# Son_of_Dark_Powersch.net
KiCad netlist of a schematic drawn in EAGLE
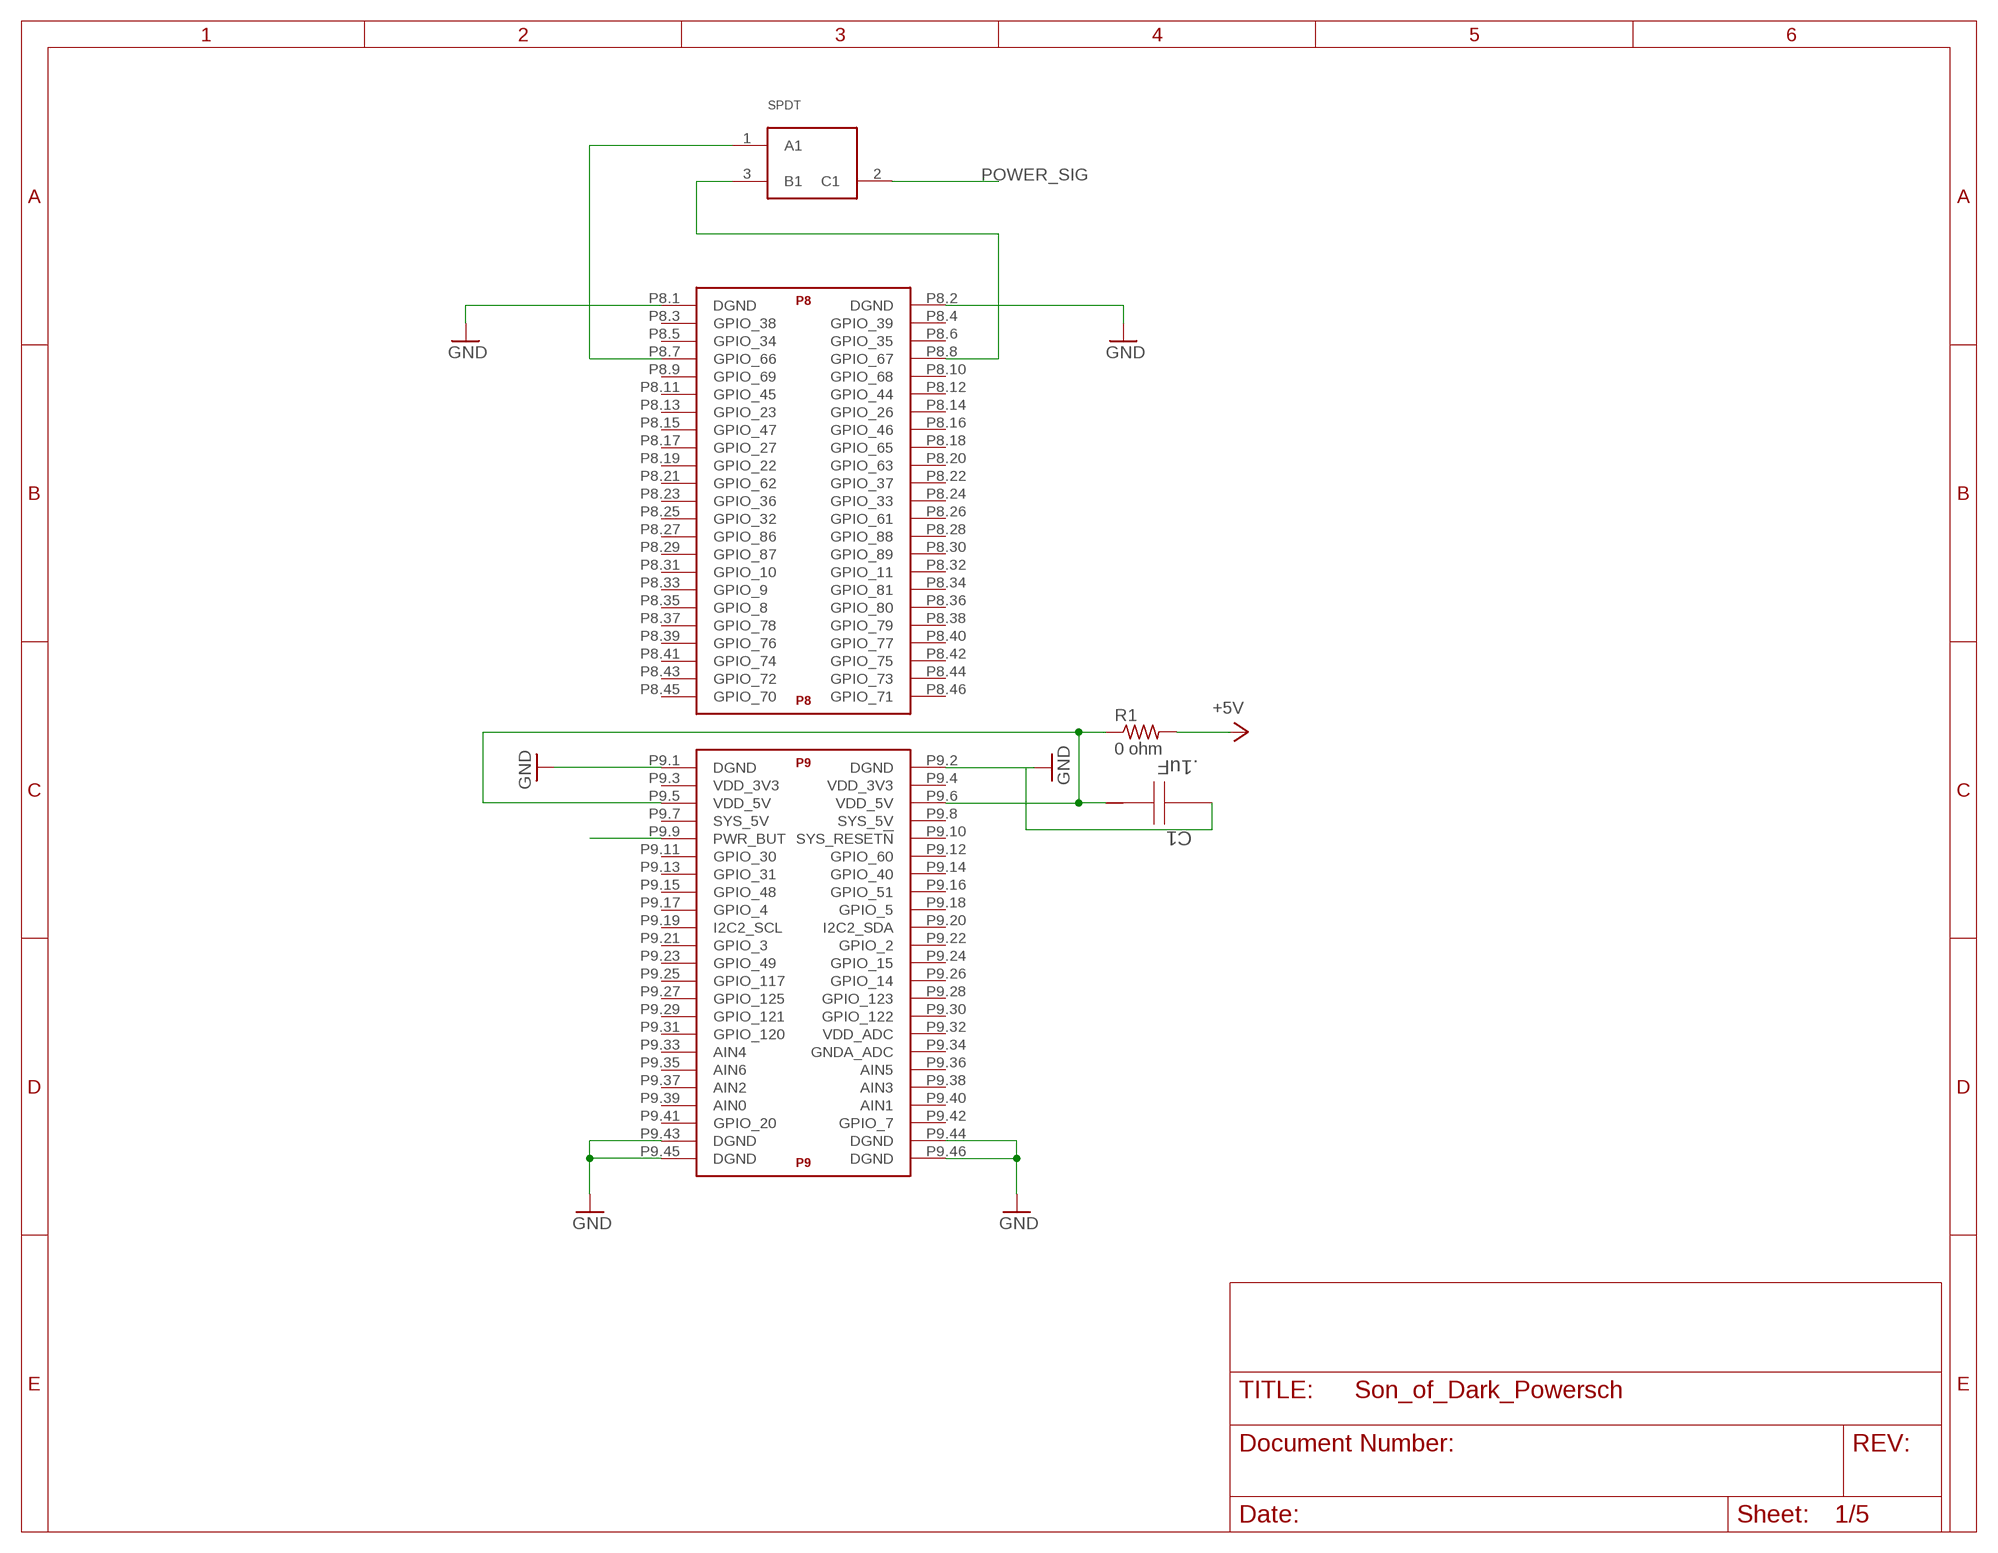
[diagram p0: schematic, sheet 1]
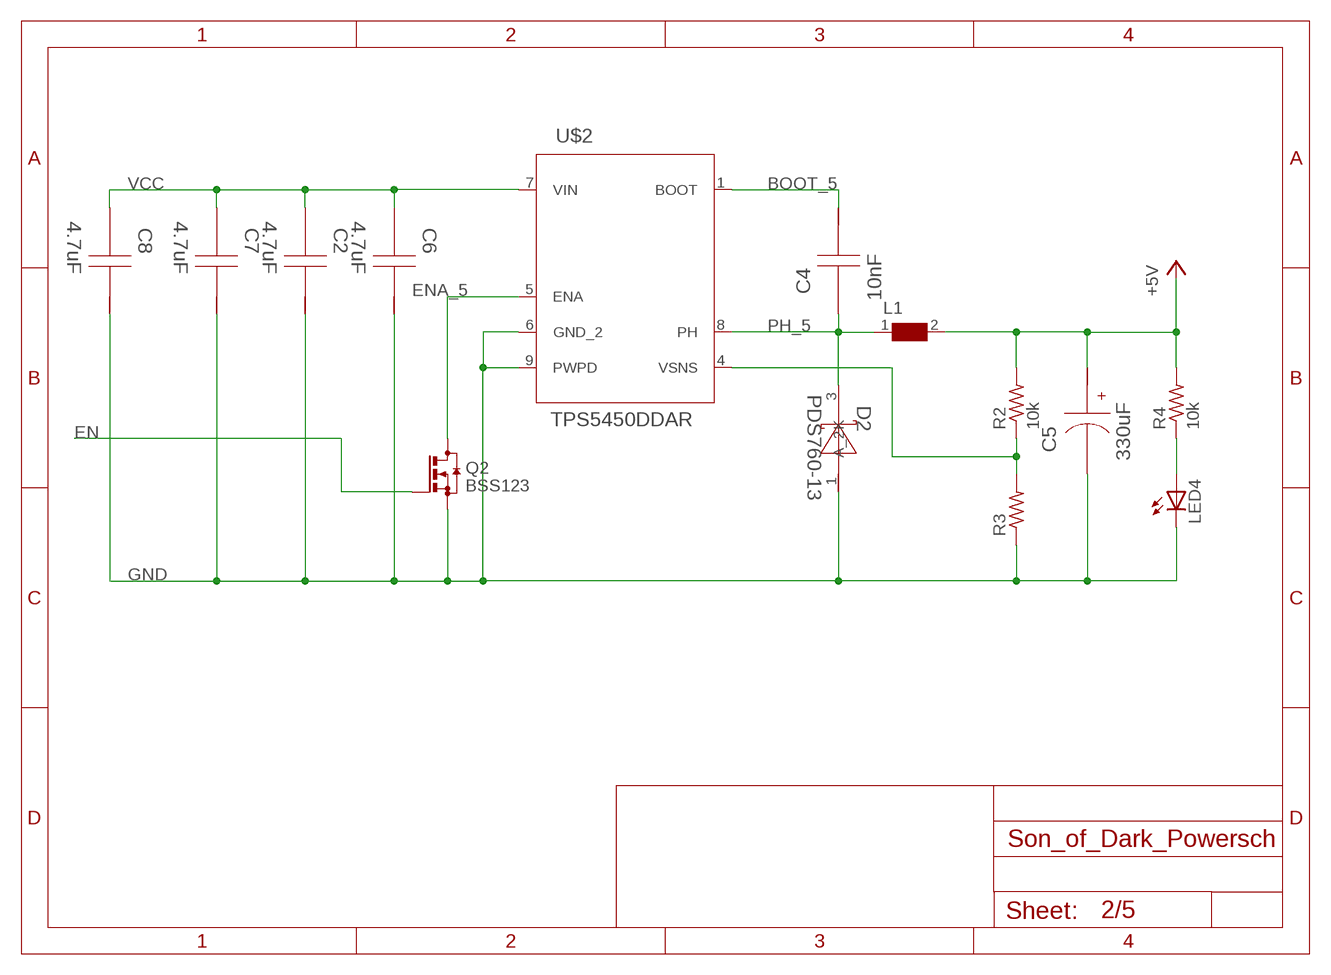
[diagram p1: schematic, sheet 2]
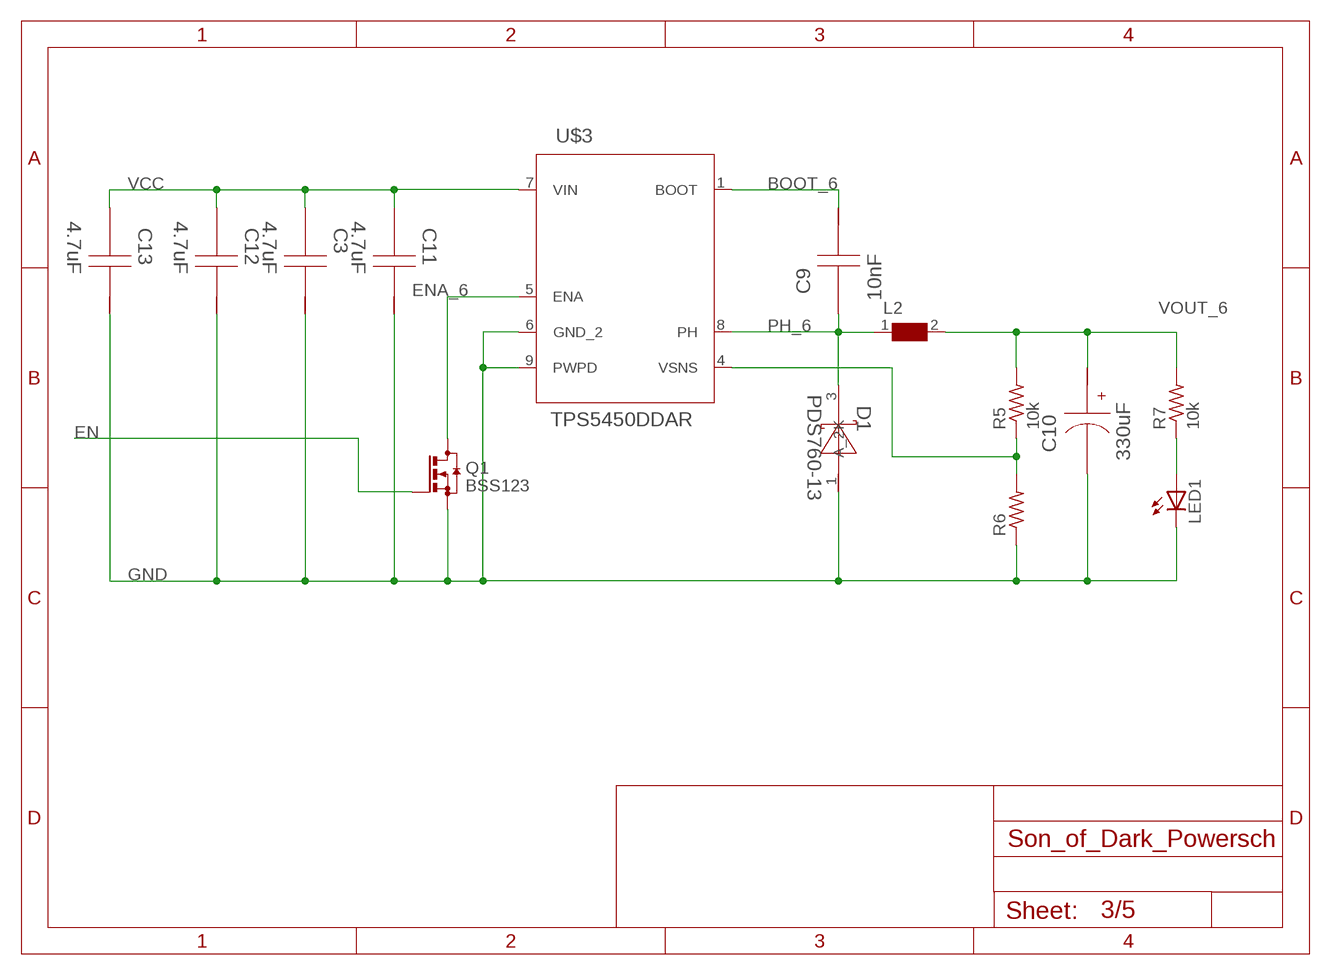
[diagram p2: schematic, sheet 3]
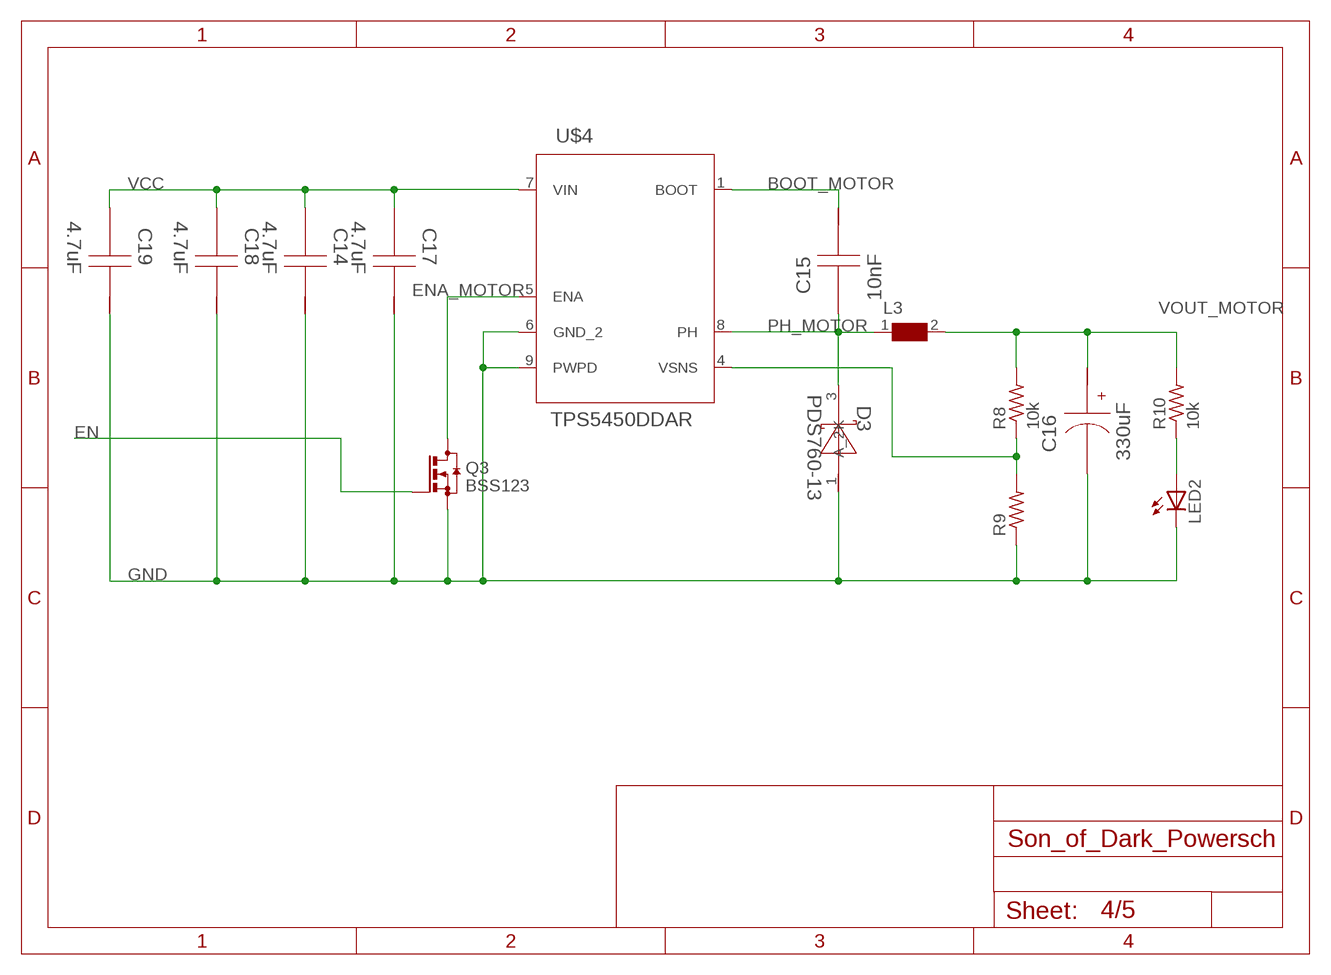
[diagram p3: schematic, sheet 4]
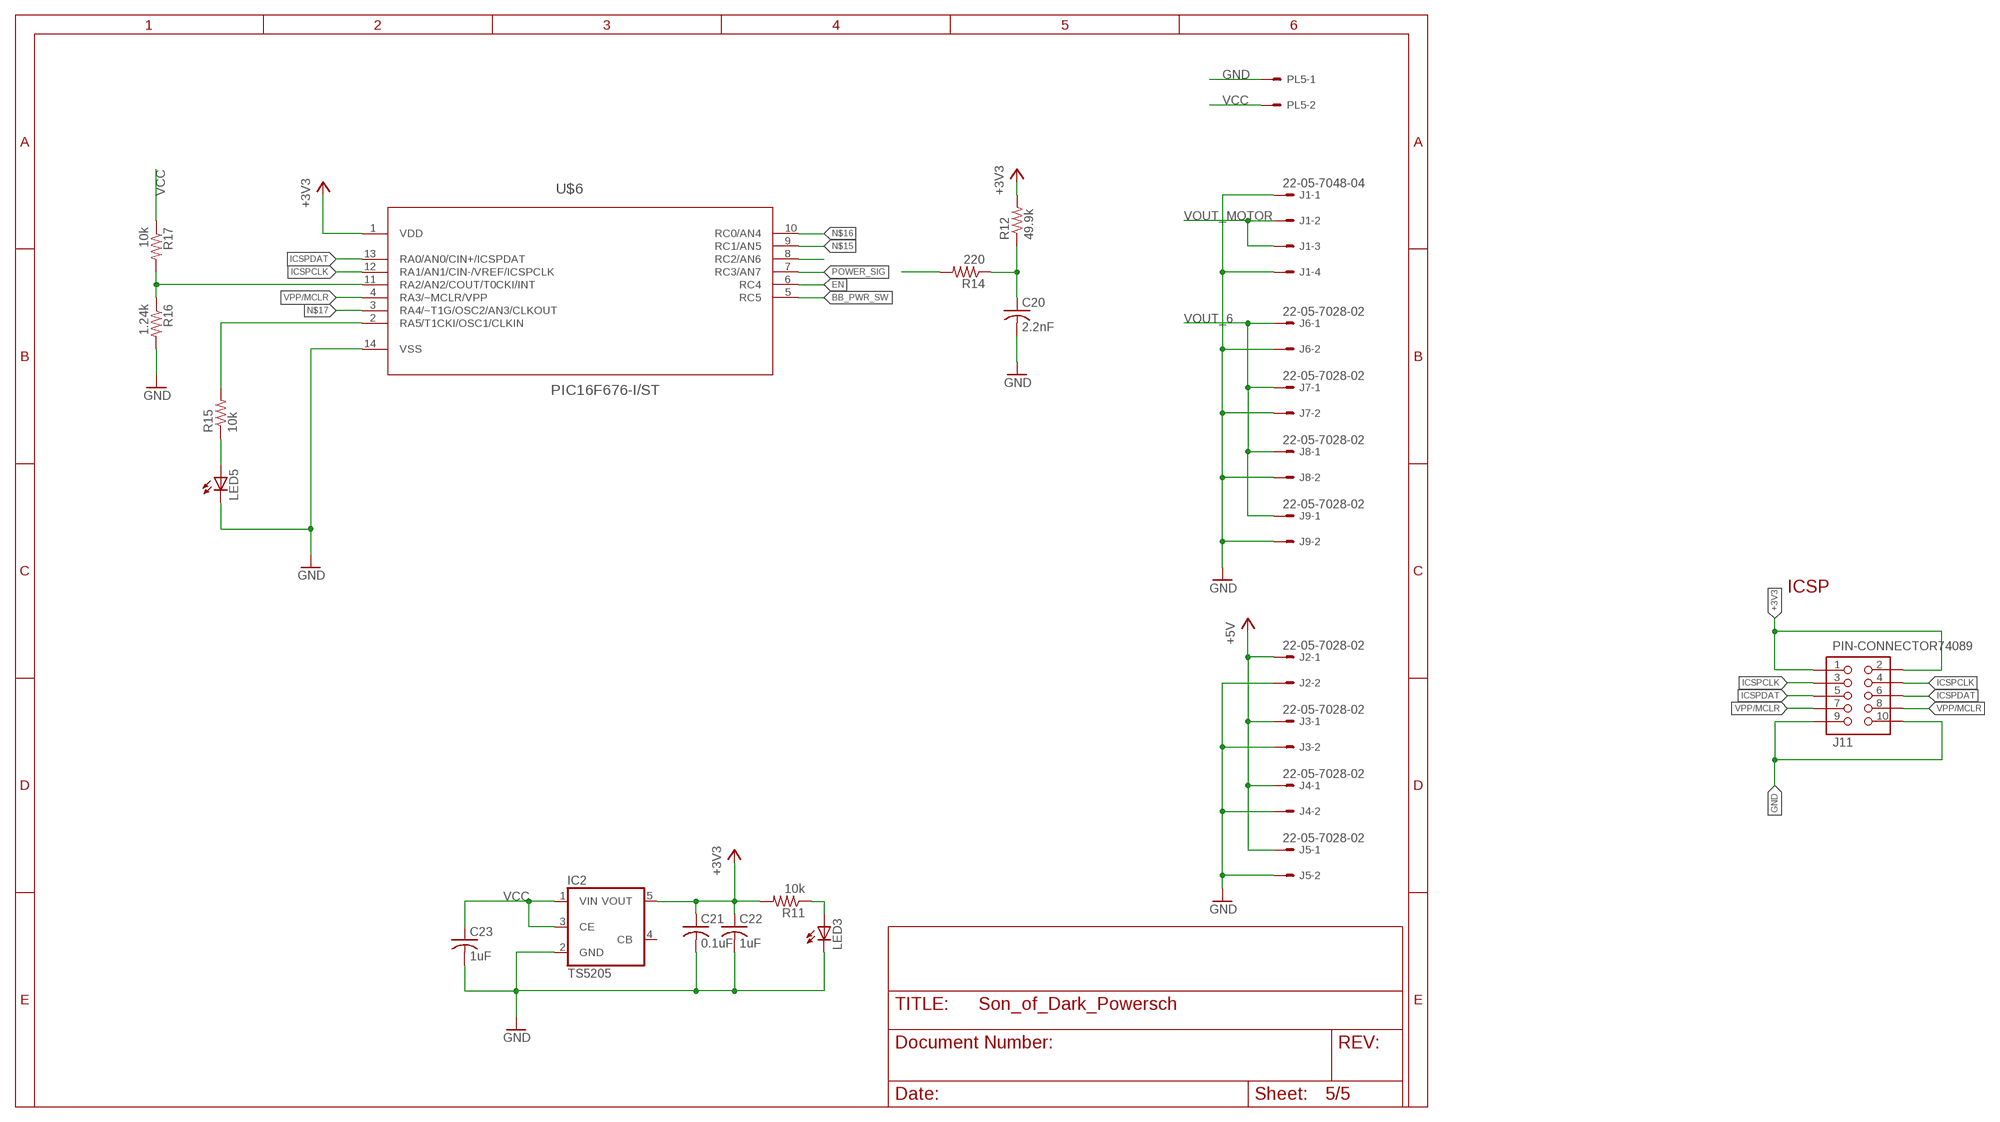
[diagram p4: schematic, sheet 5]

(export (version "E")
  (design (tool "Eeschema 10.0.6"))
  (components
    (comp (ref "C14")
      (value "4.7uF")
      (footprint "eagle-import:1206")
      (fields (field (name "MANUFACTURER_PART_NUMBER") "GRM31CR71H475KA12L"))
      (libsource (lib "eagle-import") (part "GRM31CR71H475KA12L"))
    )
    (comp (ref "C15")
      (value "10nF")
      (footprint "eagle-import:0805")
      (fields (field (name "MANUFACTURER_PART_NUMBER") "C0805C103K5RACTU"))
      (libsource (lib "eagle-import") (part "C0805C103K5RACTU"))
    )
    (comp (ref "C16")
      (value "330uF")
      (footprint "eagle-import:SM_RADIAL_10AMM")
      (fields (field (name "MANUFACTURER_PART_NUMBER") "10SVP330MX"))
      (libsource (lib "eagle-import") (part "10SVP330MX"))
    )
    (comp (ref "C17")
      (value "4.7uF")
      (footprint "eagle-import:1206")
      (fields (field (name "MANUFACTURER_PART_NUMBER") "GRM31CR71H475KA12L"))
      (libsource (lib "eagle-import") (part "GRM31CR71H475KA12L"))
    )
    (comp (ref "C18")
      (value "4.7uF")
      (footprint "eagle-import:1206")
      (fields (field (name "MANUFACTURER_PART_NUMBER") "GRM31CR71H475KA12L"))
      (libsource (lib "eagle-import") (part "GRM31CR71H475KA12L"))
    )
    (comp (ref "C19")
      (value "4.7uF")
      (footprint "eagle-import:1206")
      (fields (field (name "MANUFACTURER_PART_NUMBER") "GRM31CR71H475KA12L"))
      (libsource (lib "eagle-import") (part "GRM31CR71H475KA12L"))
    )
    (comp (ref "D3")
      (value "PDS760-13")
      (footprint "eagle-import:POWERDI5")
      (libsource (lib "eagle-import") (part "PDS760-13"))
    )
    (comp (ref "L3")
      (value "WE-HCC-7443331000_1090")
      (footprint "eagle-import:WE-HCC_1090")
      (fields (field (name "MPN") "7443331000"))
      (libsource (lib "eagle-import") (part "WE-HCC_1090-7443331000"))
    )
    (comp (ref "LED2")
      (value "LEDSML1206")
      (footprint "eagle-import:SML1206")
      (libsource (lib "eagle-import") (part "LEDSML1206"))
    )
    (comp (ref "Q3")
      (value "BSS123")
      (footprint "eagle-import:SOT23")
      (libsource (lib "eagle-import") (part "BSS123"))
    )
    (comp (ref "R8")
      (value "10k")
      (footprint "eagle-import:R1206")
      (libsource (lib "eagle-import") (part "R-US_R1206"))
    )
    (comp (ref "R9")
      (value "R-US_R1206")
      (footprint "eagle-import:R1206")
      (libsource (lib "eagle-import") (part "R-US_R1206"))
    )
    (comp (ref "R10")
      (value "10k")
      (footprint "eagle-import:R1206")
      (libsource (lib "eagle-import") (part "R-US_R1206"))
    )
    (comp (ref "U$4")
      (value "TPS5450DDAR")
      (footprint "eagle-import:R-PDSO-G8")
      (fields (field (name "MANUFACTURER_PART_NUMBER") "TPS5450DDA"))
      (libsource (lib "eagle-import") (part "TPS5450DDAR"))
    )
    (comp (ref "C20")
      (value "2.2nF")
      (footprint "eagle-import:C0603")
      (libsource (lib "eagle-import") (part "C-USC0603"))
    )
    (comp (ref "C21")
      (value "0.1uF")
      (footprint "eagle-import:C0603")
      (libsource (lib "eagle-import") (part "C-USC0603"))
    )
    (comp (ref "C22")
      (value "1uF")
      (footprint "eagle-import:C0603")
      (libsource (lib "eagle-import") (part "C-USC0603"))
    )
    (comp (ref "C23")
      (value "1uF")
      (footprint "eagle-import:C0603")
      (libsource (lib "eagle-import") (part "C-USC0603"))
    )
    (comp (ref "IC2")
      (value "TS5205")
      (footprint "eagle-import:SOT25")
      (libsource (lib "eagle-import") (part "TS5205"))
    )
    (comp (ref "J1")
      (value "22-05-7048-04")
      (footprint "eagle-import:7395-04")
      (libsource (lib "eagle-import") (part "22-?-0405-7048"))
    )
    (comp (ref "J2")
      (value "22-05-7028-02")
      (footprint "eagle-import:7395-02")
      (libsource (lib "eagle-import") (part "22-?-0205-7028"))
    )
    (comp (ref "J3")
      (value "22-05-7028-02")
      (footprint "eagle-import:7395-02")
      (libsource (lib "eagle-import") (part "22-?-0205-7028"))
    )
    (comp (ref "J4")
      (value "22-05-7028-02")
      (footprint "eagle-import:7395-02")
      (libsource (lib "eagle-import") (part "22-?-0205-7028"))
    )
    (comp (ref "J5")
      (value "22-05-7028-02")
      (footprint "eagle-import:7395-02")
      (libsource (lib "eagle-import") (part "22-?-0205-7028"))
    )
    (comp (ref "J6")
      (value "22-05-7028-02")
      (footprint "eagle-import:7395-02")
      (libsource (lib "eagle-import") (part "22-?-0205-7028"))
    )
    (comp (ref "J7")
      (value "22-05-7028-02")
      (footprint "eagle-import:7395-02")
      (libsource (lib "eagle-import") (part "22-?-0205-7028"))
    )
    (comp (ref "J8")
      (value "22-05-7028-02")
      (footprint "eagle-import:7395-02")
      (libsource (lib "eagle-import") (part "22-?-0205-7028"))
    )
    (comp (ref "J9")
      (value "22-05-7028-02")
      (footprint "eagle-import:7395-02")
      (libsource (lib "eagle-import") (part "22-?-0205-7028"))
    )
    (comp (ref "J11")
      (value "PIN-CONNECTOR74089")
      (footprint "eagle-import:10-PIN-SMD")
      (libsource (lib "eagle-import") (part "PIN-CONNECTOR74089"))
    )
    (comp (ref "LED3")
      (value "LEDSML1206")
      (footprint "eagle-import:SML1206")
      (libsource (lib "eagle-import") (part "LEDSML1206"))
    )
    (comp (ref "LED5")
      (value "LEDSML1206")
      (footprint "eagle-import:SML1206")
      (libsource (lib "eagle-import") (part "LEDSML1206"))
    )
    (comp (ref "PL5")
      (value "555X-2H")
      (footprint "eagle-import:5569-2")
      (libsource (lib "eagle-import") (part "555X-2H"))
    )
    (comp (ref "R11")
      (value "10k")
      (footprint "eagle-import:R1206")
      (libsource (lib "eagle-import") (part "R-US_R1206"))
    )
    (comp (ref "R12")
      (value "49.9k")
      (footprint "eagle-import:R0603")
      (libsource (lib "eagle-import") (part "R-US_R0603"))
    )
    (comp (ref "R14")
      (value "220")
      (footprint "eagle-import:R0603")
      (libsource (lib "eagle-import") (part "R-US_R0603"))
    )
    (comp (ref "R15")
      (value "10k")
      (footprint "eagle-import:R1206")
      (libsource (lib "eagle-import") (part "R-US_R1206"))
    )
    (comp (ref "R16")
      (value "1.24k")
      (footprint "eagle-import:R0603")
      (libsource (lib "eagle-import") (part "R-US_R0603"))
    )
    (comp (ref "R17")
      (value "10k")
      (footprint "eagle-import:R0603")
      (libsource (lib "eagle-import") (part "R-US_R0603"))
    )
    (comp (ref "U$6")
      (value "PIC16F676-I/ST")
      (footprint "eagle-import:SOP65P640X120-14N")
      (libsource (lib "eagle-import") (part "PIC16F676-I/ST"))
    )
    (comp (ref "C2")
      (value "4.7uF")
      (footprint "eagle-import:1206")
      (fields (field (name "MANUFACTURER_PART_NUMBER") "GRM31CR71H475KA12L"))
      (libsource (lib "eagle-import") (part "GRM31CR71H475KA12L"))
    )
    (comp (ref "C4")
      (value "10nF")
      (footprint "eagle-import:0805")
      (fields (field (name "MANUFACTURER_PART_NUMBER") "C0805C103K5RACTU"))
      (libsource (lib "eagle-import") (part "C0805C103K5RACTU"))
    )
    (comp (ref "C5")
      (value "330uF")
      (footprint "eagle-import:SM_RADIAL_10AMM")
      (fields (field (name "MANUFACTURER_PART_NUMBER") "10SVP330MX"))
      (libsource (lib "eagle-import") (part "10SVP330MX"))
    )
    (comp (ref "C6")
      (value "4.7uF")
      (footprint "eagle-import:1206")
      (fields (field (name "MANUFACTURER_PART_NUMBER") "GRM31CR71H475KA12L"))
      (libsource (lib "eagle-import") (part "GRM31CR71H475KA12L"))
    )
    (comp (ref "C7")
      (value "4.7uF")
      (footprint "eagle-import:1206")
      (fields (field (name "MANUFACTURER_PART_NUMBER") "GRM31CR71H475KA12L"))
      (libsource (lib "eagle-import") (part "GRM31CR71H475KA12L"))
    )
    (comp (ref "C8")
      (value "4.7uF")
      (footprint "eagle-import:1206")
      (fields (field (name "MANUFACTURER_PART_NUMBER") "GRM31CR71H475KA12L"))
      (libsource (lib "eagle-import") (part "GRM31CR71H475KA12L"))
    )
    (comp (ref "D2")
      (value "PDS760-13")
      (footprint "eagle-import:POWERDI5")
      (libsource (lib "eagle-import") (part "PDS760-13"))
    )
    (comp (ref "L1")
      (value "WE-HCC-7443331000_1090")
      (footprint "eagle-import:WE-HCC_1090")
      (fields (field (name "MPN") "7443331000"))
      (libsource (lib "eagle-import") (part "WE-HCC_1090-7443331000"))
    )
    (comp (ref "LED4")
      (value "LEDSML1206")
      (footprint "eagle-import:SML1206")
      (libsource (lib "eagle-import") (part "LEDSML1206"))
    )
    (comp (ref "Q2")
      (value "BSS123")
      (footprint "eagle-import:SOT23")
      (libsource (lib "eagle-import") (part "BSS123"))
    )
    (comp (ref "R2")
      (value "10k")
      (footprint "eagle-import:R1206")
      (libsource (lib "eagle-import") (part "R-US_R1206"))
    )
    (comp (ref "R3")
      (value "R-US_R1206")
      (footprint "eagle-import:R1206")
      (libsource (lib "eagle-import") (part "R-US_R1206"))
    )
    (comp (ref "R4")
      (value "10k")
      (footprint "eagle-import:R1206")
      (libsource (lib "eagle-import") (part "R-US_R1206"))
    )
    (comp (ref "U$2")
      (value "TPS5450DDAR")
      (footprint "eagle-import:R-PDSO-G8")
      (fields (field (name "MANUFACTURER_PART_NUMBER") "TPS5450DDA"))
      (libsource (lib "eagle-import") (part "TPS5450DDAR"))
    )
    (comp (ref "C3")
      (value "4.7uF")
      (footprint "eagle-import:1206")
      (fields (field (name "MANUFACTURER_PART_NUMBER") "GRM31CR71H475KA12L"))
      (libsource (lib "eagle-import") (part "GRM31CR71H475KA12L"))
    )
    (comp (ref "C9")
      (value "10nF")
      (footprint "eagle-import:0805")
      (fields (field (name "MANUFACTURER_PART_NUMBER") "C0805C103K5RACTU"))
      (libsource (lib "eagle-import") (part "C0805C103K5RACTU"))
    )
    (comp (ref "C10")
      (value "330uF")
      (footprint "eagle-import:SM_RADIAL_10AMM")
      (fields (field (name "MANUFACTURER_PART_NUMBER") "10SVP330MX"))
      (libsource (lib "eagle-import") (part "10SVP330MX"))
    )
    (comp (ref "C11")
      (value "4.7uF")
      (footprint "eagle-import:1206")
      (fields (field (name "MANUFACTURER_PART_NUMBER") "GRM31CR71H475KA12L"))
      (libsource (lib "eagle-import") (part "GRM31CR71H475KA12L"))
    )
    (comp (ref "C12")
      (value "4.7uF")
      (footprint "eagle-import:1206")
      (fields (field (name "MANUFACTURER_PART_NUMBER") "GRM31CR71H475KA12L"))
      (libsource (lib "eagle-import") (part "GRM31CR71H475KA12L"))
    )
    (comp (ref "C13")
      (value "4.7uF")
      (footprint "eagle-import:1206")
      (fields (field (name "MANUFACTURER_PART_NUMBER") "GRM31CR71H475KA12L"))
      (libsource (lib "eagle-import") (part "GRM31CR71H475KA12L"))
    )
    (comp (ref "D1")
      (value "PDS760-13")
      (footprint "eagle-import:POWERDI5")
      (libsource (lib "eagle-import") (part "PDS760-13"))
    )
    (comp (ref "L2")
      (value "WE-HCC-7443331000_1090")
      (footprint "eagle-import:WE-HCC_1090")
      (fields (field (name "MPN") "7443331000"))
      (libsource (lib "eagle-import") (part "WE-HCC_1090-7443331000"))
    )
    (comp (ref "LED1")
      (value "LEDSML1206")
      (footprint "eagle-import:SML1206")
      (libsource (lib "eagle-import") (part "LEDSML1206"))
    )
    (comp (ref "Q1")
      (value "BSS123")
      (footprint "eagle-import:SOT23")
      (libsource (lib "eagle-import") (part "BSS123"))
    )
    (comp (ref "R5")
      (value "10k")
      (footprint "eagle-import:R1206")
      (libsource (lib "eagle-import") (part "R-US_R1206"))
    )
    (comp (ref "R6")
      (value "R-US_R1206")
      (footprint "eagle-import:R1206")
      (libsource (lib "eagle-import") (part "R-US_R1206"))
    )
    (comp (ref "R7")
      (value "10k")
      (footprint "eagle-import:R1206")
      (libsource (lib "eagle-import") (part "R-US_R1206"))
    )
    (comp (ref "U$3")
      (value "TPS5450DDAR")
      (footprint "eagle-import:R-PDSO-G8")
      (fields (field (name "MANUFACTURER_PART_NUMBER") "TPS5450DDA"))
      (libsource (lib "eagle-import") (part "TPS5450DDAR"))
    )
    (comp (ref "C1")
      (value ".1uF")
      (footprint "eagle-import:1206")
      (fields (field (name "MANUFACTURER_PART_NUMBER") "C3216X5R1A106K"))
      (libsource (lib "eagle-import") (part "C3216X5R1A106K"))
    )
    (comp (ref "R1")
      (value "0 ohm")
      (footprint "eagle-import:R1206")
      (libsource (lib "eagle-import") (part "R-US_R1206"))
    )
    (comp (ref "SPDT")
      (value "SPDT_SWITCH")
      (footprint "eagle-import:SPDT")
      (libsource (lib "eagle-import") (part "SPDT_SWITCH"))
    )
    (comp (ref "U$1")
      (value "BEAGLE_BONE_BLACK_CAPE")
      (footprint "eagle-import:BEAGLE_BONE_BLACK_CAPE")
      (libsource (lib "eagle-import") (part "BEAGLE_BONE_BLACK_CAPE"))
    )
  )
  (nets
    (net (code "1") (name "+3V3") (class "Default")
      (node (ref "C21") (pin "1") (pinfunction "1_1") (pintype "passive"))
      (node (ref "C22") (pin "1") (pinfunction "1_1") (pintype "passive"))
      (node (ref "IC2") (pin "5") (pinfunction "VOUT_5") (pintype "passive"))
      (node (ref "J11") (pin "1") (pinfunction "P$1_1") (pintype "power_in"))
      (node (ref "J11") (pin "2") (pinfunction "P$2_2") (pintype "power_in"))
      (node (ref "R11") (pin "2") (pinfunction "2_2") (pintype "passive"))
      (node (ref "R12") (pin "2") (pinfunction "2_2") (pintype "passive"))
      (node (ref "U$6") (pin "1") (pinfunction "VDD_1") (pintype "power_in"))
    )
    (net (code "2") (name "+5V") (class "Default")
      (node (ref "C5") (pin "1") (pinfunction "+_1") (pintype "passive"))
      (node (ref "J2") (pin "1") (pinfunction "S_1") (pintype "passive"))
      (node (ref "J3") (pin "1") (pinfunction "S_1") (pintype "passive"))
      (node (ref "J4") (pin "1") (pinfunction "S_1") (pintype "passive"))
      (node (ref "J5") (pin "1") (pinfunction "S_1") (pintype "passive"))
      (node (ref "L1") (pin "2") (pinfunction "2_2") (pintype "passive"))
      (node (ref "R1") (pin "2") (pinfunction "2_2") (pintype "passive"))
      (node (ref "R2") (pin "2") (pinfunction "2_2") (pintype "passive"))
      (node (ref "R4") (pin "2") (pinfunction "2_2") (pintype "passive"))
    )
    (net (code "3") (name "BB_PWR_SW") (class "Default")
      (node (ref "U$1") (pin "P9.9") (pinfunction "PWR_BUT_P9.9") (pintype "bidirectional"))
      (node (ref "U$6") (pin "5") (pinfunction "RC5_5") (pintype "bidirectional"))
    )
    (net (code "4") (name "BOOT_5") (class "Default")
      (node (ref "C4") (pin "1") (pinfunction "1_1") (pintype "passive"))
      (node (ref "U$2") (pin "1") (pinfunction "BOOT_1") (pintype "passive"))
    )
    (net (code "5") (name "BOOT_6") (class "Default")
      (node (ref "C9") (pin "1") (pinfunction "1_1") (pintype "passive"))
      (node (ref "U$3") (pin "1") (pinfunction "BOOT_1") (pintype "passive"))
    )
    (net (code "6") (name "BOOT_MOTOR") (class "Default")
      (node (ref "C15") (pin "1") (pinfunction "1_1") (pintype "passive"))
      (node (ref "U$4") (pin "1") (pinfunction "BOOT_1") (pintype "passive"))
    )
    (net (code "7") (name "EN") (class "Default")
      (node (ref "Q1") (pin "1") (pinfunction "G_1") (pintype "passive"))
      (node (ref "Q2") (pin "1") (pinfunction "G_1") (pintype "passive"))
      (node (ref "Q3") (pin "1") (pinfunction "G_1") (pintype "passive"))
      (node (ref "U$6") (pin "6") (pinfunction "RC4_6") (pintype "bidirectional"))
    )
    (net (code "8") (name "ENA_5") (class "Default")
      (node (ref "Q2") (pin "3") (pinfunction "D_3") (pintype "passive"))
      (node (ref "U$2") (pin "5") (pinfunction "ENA_5") (pintype "passive"))
    )
    (net (code "9") (name "ENA_6") (class "Default")
      (node (ref "Q1") (pin "3") (pinfunction "D_3") (pintype "passive"))
      (node (ref "U$3") (pin "5") (pinfunction "ENA_5") (pintype "passive"))
    )
    (net (code "10") (name "ENA_MOTOR") (class "Default")
      (node (ref "Q3") (pin "3") (pinfunction "D_3") (pintype "passive"))
      (node (ref "U$4") (pin "5") (pinfunction "ENA_5") (pintype "passive"))
    )
    (net (code "11") (name "GND") (class "Default")
      (node (ref "C1") (pin "2") (pinfunction "2_2") (pintype "passive"))
      (node (ref "C10") (pin "2") (pinfunction "-_2") (pintype "passive"))
      (node (ref "C11") (pin "1") (pinfunction "1_1") (pintype "passive"))
      (node (ref "C12") (pin "1") (pinfunction "1_1") (pintype "passive"))
      (node (ref "C13") (pin "1") (pinfunction "1_1") (pintype "passive"))
      (node (ref "C14") (pin "1") (pinfunction "1_1") (pintype "passive"))
      (node (ref "C16") (pin "2") (pinfunction "-_2") (pintype "passive"))
      (node (ref "C17") (pin "1") (pinfunction "1_1") (pintype "passive"))
      (node (ref "C18") (pin "1") (pinfunction "1_1") (pintype "passive"))
      (node (ref "C19") (pin "1") (pinfunction "1_1") (pintype "passive"))
      (node (ref "C2") (pin "1") (pinfunction "1_1") (pintype "passive"))
      (node (ref "C20") (pin "2") (pinfunction "2_2") (pintype "passive"))
      (node (ref "C21") (pin "2") (pinfunction "2_2") (pintype "passive"))
      (node (ref "C22") (pin "2") (pinfunction "2_2") (pintype "passive"))
      (node (ref "C23") (pin "2") (pinfunction "2_2") (pintype "passive"))
      (node (ref "C3") (pin "1") (pinfunction "1_1") (pintype "passive"))
      (node (ref "C5") (pin "2") (pinfunction "-_2") (pintype "passive"))
      (node (ref "C6") (pin "1") (pinfunction "1_1") (pintype "passive"))
      (node (ref "C7") (pin "1") (pinfunction "1_1") (pintype "passive"))
      (node (ref "C8") (pin "1") (pinfunction "1_1") (pintype "passive"))
      (node (ref "D1") (pin "1") (pinfunction "A_2_1") (pintype "passive"))
      (node (ref "D2") (pin "1") (pinfunction "A_2_1") (pintype "passive"))
      (node (ref "D3") (pin "1") (pinfunction "A_2_1") (pintype "passive"))
      (node (ref "IC2") (pin "2") (pinfunction "GND_2") (pintype "passive"))
      (node (ref "J1") (pin "1") (pinfunction "S_1") (pintype "passive"))
      (node (ref "J1") (pin "4") (pinfunction "S_4") (pintype "passive"))
      (node (ref "J11") (pin "10") (pinfunction "P$10_10") (pintype "power_in"))
      (node (ref "J11") (pin "9") (pinfunction "P$9_9") (pintype "power_in"))
      (node (ref "J2") (pin "2") (pinfunction "S_2") (pintype "passive"))
      (node (ref "J3") (pin "2") (pinfunction "S_2") (pintype "passive"))
      (node (ref "J4") (pin "2") (pinfunction "S_2") (pintype "passive"))
      (node (ref "J5") (pin "2") (pinfunction "S_2") (pintype "passive"))
      (node (ref "J6") (pin "2") (pinfunction "S_2") (pintype "passive"))
      (node (ref "J7") (pin "2") (pinfunction "S_2") (pintype "passive"))
      (node (ref "J8") (pin "2") (pinfunction "S_2") (pintype "passive"))
      (node (ref "J9") (pin "2") (pinfunction "S_2") (pintype "passive"))
      (node (ref "LED1") (pin "C") (pinfunction "C_C") (pintype "passive"))
      (node (ref "LED2") (pin "C") (pinfunction "C_C") (pintype "passive"))
      (node (ref "LED3") (pin "C") (pinfunction "C_C") (pintype "passive"))
      (node (ref "LED4") (pin "C") (pinfunction "C_C") (pintype "passive"))
      (node (ref "LED5") (pin "C") (pinfunction "C_C") (pintype "passive"))
      (node (ref "PL5") (pin "1") (pinfunction "S_1") (pintype "passive"))
      (node (ref "Q1") (pin "2") (pinfunction "S_2") (pintype "passive"))
      (node (ref "Q2") (pin "2") (pinfunction "S_2") (pintype "passive"))
      (node (ref "Q3") (pin "2") (pinfunction "S_2") (pintype "passive"))
      (node (ref "R16") (pin "2") (pinfunction "2_2") (pintype "passive"))
      (node (ref "R3") (pin "1") (pinfunction "1_1") (pintype "passive"))
      (node (ref "R6") (pin "1") (pinfunction "1_1") (pintype "passive"))
      (node (ref "R9") (pin "1") (pinfunction "1_1") (pintype "passive"))
      (node (ref "U$1") (pin "P8.1") (pinfunction "DGND_P8.1") (pintype "bidirectional"))
      (node (ref "U$1") (pin "P8.2") (pinfunction "DGND_P8.2") (pintype "bidirectional"))
      (node (ref "U$1") (pin "P9.1") (pinfunction "DGND_P9.1") (pintype "bidirectional"))
      (node (ref "U$1") (pin "P9.2") (pinfunction "DGND_P9.2") (pintype "bidirectional"))
      (node (ref "U$1") (pin "P9.43") (pinfunction "DGND_P9.43") (pintype "bidirectional"))
      (node (ref "U$1") (pin "P9.44") (pinfunction "DGND_P9.44") (pintype "bidirectional"))
      (node (ref "U$1") (pin "P9.45") (pinfunction "DGND_P9.45") (pintype "bidirectional"))
      (node (ref "U$1") (pin "P9.46") (pinfunction "DGND_P9.46") (pintype "bidirectional"))
      (node (ref "U$2") (pin "6") (pinfunction "GND_2_6") (pintype "passive"))
      (node (ref "U$2") (pin "9") (pinfunction "PWPD_9") (pintype "passive"))
      (node (ref "U$3") (pin "6") (pinfunction "GND_2_6") (pintype "passive"))
      (node (ref "U$3") (pin "9") (pinfunction "PWPD_9") (pintype "passive"))
      (node (ref "U$4") (pin "6") (pinfunction "GND_2_6") (pintype "passive"))
      (node (ref "U$4") (pin "9") (pinfunction "PWPD_9") (pintype "passive"))
      (node (ref "U$6") (pin "14") (pinfunction "VSS_14") (pintype "power_in"))
    )
    (net (code "12") (name "ICSPCLK") (class "Default")
      (node (ref "J11") (pin "3") (pinfunction "P$3_3") (pintype "power_in"))
      (node (ref "J11") (pin "4") (pinfunction "P$4_4") (pintype "power_in"))
      (node (ref "U$6") (pin "12") (pinfunction "RA1/AN1/CIN-/VREF/ICSPCLK_12") (pintype "bidirectional"))
    )
    (net (code "13") (name "ICSPDAT") (class "Default")
      (node (ref "J11") (pin "5") (pinfunction "P$5_5") (pintype "power_in"))
      (node (ref "J11") (pin "6") (pinfunction "P$6_6") (pintype "power_in"))
      (node (ref "U$6") (pin "13") (pinfunction "RA0/AN0/CIN+/ICSPDAT_13") (pintype "bidirectional"))
    )
    (net (code "14") (name "N$15") (class "Default")
      (node (ref "U$6") (pin "9") (pinfunction "RC1/AN5_9") (pintype "bidirectional"))
    )
    (net (code "15") (name "N$16") (class "Default")
      (node (ref "U$6") (pin "10") (pinfunction "RC0/AN4_10") (pintype "bidirectional"))
    )
    (net (code "16") (name "N$17") (class "Default")
      (node (ref "U$6") (pin "3") (pinfunction "RA4/~{T1G/OSC2/AN3/CLKOUT}_3") (pintype "bidirectional"))
    )
    (net (code "17") (name "Net-(C1-Pad1)") (class "Default")
      (node (ref "C1") (pin "1") (pinfunction "1_1") (pintype "passive"))
      (node (ref "R1") (pin "1") (pinfunction "1_1") (pintype "passive"))
      (node (ref "U$1") (pin "P9.5") (pinfunction "VDD_5V_P9.5") (pintype "bidirectional"))
      (node (ref "U$1") (pin "P9.6") (pinfunction "VDD_5V_P9.6") (pintype "bidirectional"))
    )
    (net (code "18") (name "Net-(C20-Pad1)") (class "Default")
      (node (ref "C20") (pin "1") (pinfunction "1_1") (pintype "passive"))
      (node (ref "R12") (pin "1") (pinfunction "1_1") (pintype "passive"))
      (node (ref "R14") (pin "1") (pinfunction "1_1") (pintype "passive"))
    )
    (net (code "19") (name "Net-(LED1-PadA)") (class "Default")
      (node (ref "LED1") (pin "A") (pinfunction "A_A") (pintype "passive"))
      (node (ref "R7") (pin "1") (pinfunction "1_1") (pintype "passive"))
    )
    (net (code "20") (name "Net-(LED2-PadA)") (class "Default")
      (node (ref "LED2") (pin "A") (pinfunction "A_A") (pintype "passive"))
      (node (ref "R10") (pin "1") (pinfunction "1_1") (pintype "passive"))
    )
    (net (code "21") (name "Net-(LED3-PadA)") (class "Default")
      (node (ref "LED3") (pin "A") (pinfunction "A_A") (pintype "passive"))
      (node (ref "R11") (pin "1") (pinfunction "1_1") (pintype "passive"))
    )
    (net (code "22") (name "Net-(LED4-PadA)") (class "Default")
      (node (ref "LED4") (pin "A") (pinfunction "A_A") (pintype "passive"))
      (node (ref "R4") (pin "1") (pinfunction "1_1") (pintype "passive"))
    )
    (net (code "23") (name "Net-(LED5-PadA)") (class "Default")
      (node (ref "LED5") (pin "A") (pinfunction "A_A") (pintype "passive"))
      (node (ref "R15") (pin "1") (pinfunction "1_1") (pintype "passive"))
    )
    (net (code "24") (name "Net-(SPDT-A1)") (class "Default")
      (node (ref "SPDT") (pin "1") (pinfunction "A1_1") (pintype "bidirectional"))
      (node (ref "U$1") (pin "P8.7") (pinfunction "GPIO_66_P8.7") (pintype "bidirectional"))
    )
    (net (code "25") (name "Net-(SPDT-B1)") (class "Default")
      (node (ref "SPDT") (pin "3") (pinfunction "B1_3") (pintype "bidirectional"))
      (node (ref "U$1") (pin "P8.8") (pinfunction "GPIO_67_P8.8") (pintype "bidirectional"))
    )
    (net (code "26") (name "Net-(U$2-VSNS)") (class "Default")
      (node (ref "R2") (pin "1") (pinfunction "1_1") (pintype "passive"))
      (node (ref "R3") (pin "2") (pinfunction "2_2") (pintype "passive"))
      (node (ref "U$2") (pin "4") (pinfunction "VSNS_4") (pintype "passive"))
    )
    (net (code "27") (name "Net-(U$3-VSNS)") (class "Default")
      (node (ref "R5") (pin "1") (pinfunction "1_1") (pintype "passive"))
      (node (ref "R6") (pin "2") (pinfunction "2_2") (pintype "passive"))
      (node (ref "U$3") (pin "4") (pinfunction "VSNS_4") (pintype "passive"))
    )
    (net (code "28") (name "Net-(U$4-VSNS)") (class "Default")
      (node (ref "R8") (pin "1") (pinfunction "1_1") (pintype "passive"))
      (node (ref "R9") (pin "2") (pinfunction "2_2") (pintype "passive"))
      (node (ref "U$4") (pin "4") (pinfunction "VSNS_4") (pintype "passive"))
    )
    (net (code "29") (name "Net-(U$6-RA2{slash}AN2{slash}COUT{slash}T0CKI{slash}INT)") (class "Default")
      (node (ref "R16") (pin "1") (pinfunction "1_1") (pintype "passive"))
      (node (ref "R17") (pin "2") (pinfunction "2_2") (pintype "passive"))
      (node (ref "U$6") (pin "11") (pinfunction "RA2/AN2/COUT/T0CKI/INT_11") (pintype "bidirectional"))
    )
    (net (code "30") (name "Net-(U$6-RA5{slash}T1CKI{slash}OSC1{slash}CLKIN)") (class "Default")
      (node (ref "R15") (pin "2") (pinfunction "2_2") (pintype "passive"))
      (node (ref "U$6") (pin "2") (pinfunction "RA5/T1CKI/OSC1/CLKIN_2") (pintype "bidirectional"))
    )
    (net (code "31") (name "PH_5") (class "Default")
      (node (ref "C4") (pin "2") (pinfunction "2_2") (pintype "passive"))
      (node (ref "D2") (pin "3") (pinfunction "K_3") (pintype "passive"))
      (node (ref "L1") (pin "1") (pinfunction "1_1") (pintype "passive"))
      (node (ref "U$2") (pin "8") (pinfunction "PH_8") (pintype "passive"))
    )
    (net (code "32") (name "PH_6") (class "Default")
      (node (ref "C9") (pin "2") (pinfunction "2_2") (pintype "passive"))
      (node (ref "D1") (pin "3") (pinfunction "K_3") (pintype "passive"))
      (node (ref "L2") (pin "1") (pinfunction "1_1") (pintype "passive"))
      (node (ref "U$3") (pin "8") (pinfunction "PH_8") (pintype "passive"))
    )
    (net (code "33") (name "PH_MOTOR") (class "Default")
      (node (ref "C15") (pin "2") (pinfunction "2_2") (pintype "passive"))
      (node (ref "D3") (pin "3") (pinfunction "K_3") (pintype "passive"))
      (node (ref "L3") (pin "1") (pinfunction "1_1") (pintype "passive"))
      (node (ref "U$4") (pin "8") (pinfunction "PH_8") (pintype "passive"))
    )
    (net (code "34") (name "POWER_SIG") (class "Default")
      (node (ref "SPDT") (pin "2") (pinfunction "C1_2") (pintype "bidirectional"))
      (node (ref "U$6") (pin "7") (pinfunction "RC3/AN7_7") (pintype "bidirectional"))
    )
    (net (code "35") (name "VCC") (class "Default")
      (node (ref "C11") (pin "2") (pinfunction "2_2") (pintype "passive"))
      (node (ref "C12") (pin "2") (pinfunction "2_2") (pintype "passive"))
      (node (ref "C13") (pin "2") (pinfunction "2_2") (pintype "passive"))
      (node (ref "C14") (pin "2") (pinfunction "2_2") (pintype "passive"))
      (node (ref "C17") (pin "2") (pinfunction "2_2") (pintype "passive"))
      (node (ref "C18") (pin "2") (pinfunction "2_2") (pintype "passive"))
      (node (ref "C19") (pin "2") (pinfunction "2_2") (pintype "passive"))
      (node (ref "C2") (pin "2") (pinfunction "2_2") (pintype "passive"))
      (node (ref "C23") (pin "1") (pinfunction "1_1") (pintype "passive"))
      (node (ref "C3") (pin "2") (pinfunction "2_2") (pintype "passive"))
      (node (ref "C6") (pin "2") (pinfunction "2_2") (pintype "passive"))
      (node (ref "C7") (pin "2") (pinfunction "2_2") (pintype "passive"))
      (node (ref "C8") (pin "2") (pinfunction "2_2") (pintype "passive"))
      (node (ref "IC2") (pin "1") (pinfunction "VIN_1") (pintype "input"))
      (node (ref "IC2") (pin "3") (pinfunction "CE_3") (pintype "input"))
      (node (ref "PL5") (pin "2") (pinfunction "S_2") (pintype "passive"))
      (node (ref "R17") (pin "1") (pinfunction "1_1") (pintype "passive"))
      (node (ref "U$2") (pin "7") (pinfunction "VIN_7") (pintype "passive"))
      (node (ref "U$3") (pin "7") (pinfunction "VIN_7") (pintype "passive"))
      (node (ref "U$4") (pin "7") (pinfunction "VIN_7") (pintype "passive"))
    )
    (net (code "36") (name "VOUT_6") (class "Default")
      (node (ref "C10") (pin "1") (pinfunction "+_1") (pintype "passive"))
      (node (ref "J6") (pin "1") (pinfunction "S_1") (pintype "passive"))
      (node (ref "J7") (pin "1") (pinfunction "S_1") (pintype "passive"))
      (node (ref "J8") (pin "1") (pinfunction "S_1") (pintype "passive"))
      (node (ref "J9") (pin "1") (pinfunction "S_1") (pintype "passive"))
      (node (ref "L2") (pin "2") (pinfunction "2_2") (pintype "passive"))
      (node (ref "R5") (pin "2") (pinfunction "2_2") (pintype "passive"))
      (node (ref "R7") (pin "2") (pinfunction "2_2") (pintype "passive"))
    )
    (net (code "37") (name "VOUT_MOTOR") (class "Default")
      (node (ref "C16") (pin "1") (pinfunction "+_1") (pintype "passive"))
      (node (ref "J1") (pin "2") (pinfunction "S_2") (pintype "passive"))
      (node (ref "J1") (pin "3") (pinfunction "S_3") (pintype "passive"))
      (node (ref "L3") (pin "2") (pinfunction "2_2") (pintype "passive"))
      (node (ref "R10") (pin "2") (pinfunction "2_2") (pintype "passive"))
      (node (ref "R8") (pin "2") (pinfunction "2_2") (pintype "passive"))
    )
    (net (code "38") (name "VPP{slash}MCLR") (class "Default")
      (node (ref "J11") (pin "7") (pinfunction "P$7_7") (pintype "power_in"))
      (node (ref "J11") (pin "8") (pinfunction "P$8_8") (pintype "power_in"))
      (node (ref "R14") (pin "2") (pinfunction "2_2") (pintype "passive"))
      (node (ref "U$6") (pin "4") (pinfunction "RA3/~{MCLR/VPP}_4") (pintype "bidirectional"))
    )
    (net (code "39") (name "unconnected-(IC2-CB-Pad4)") (class "Default")
      (node (ref "IC2") (pin "4") (pinfunction "CB_4") (pintype "input"))
    )
    (net (code "40") (name "unconnected-(U$1A-GPIO_8-PadP8.35)") (class "Default")
      (node (ref "U$1") (pin "P8.35") (pinfunction "GPIO_8_P8.35") (pintype "bidirectional"))
    )
    (net (code "41") (name "unconnected-(U$1A-GPIO_9-PadP8.33)") (class "Default")
      (node (ref "U$1") (pin "P8.33") (pinfunction "GPIO_9_P8.33") (pintype "bidirectional"))
    )
    (net (code "42") (name "unconnected-(U$1A-GPIO_10-PadP8.31)") (class "Default")
      (node (ref "U$1") (pin "P8.31") (pinfunction "GPIO_10_P8.31") (pintype "bidirectional"))
    )
    (net (code "43") (name "unconnected-(U$1A-GPIO_11-PadP8.32)") (class "Default")
      (node (ref "U$1") (pin "P8.32") (pinfunction "GPIO_11_P8.32") (pintype "bidirectional"))
    )
    (net (code "44") (name "unconnected-(U$1A-GPIO_22-PadP8.19)") (class "Default")
      (node (ref "U$1") (pin "P8.19") (pinfunction "GPIO_22_P8.19") (pintype "bidirectional"))
    )
    (net (code "45") (name "unconnected-(U$1A-GPIO_23-PadP8.13)") (class "Default")
      (node (ref "U$1") (pin "P8.13") (pinfunction "GPIO_23_P8.13") (pintype "bidirectional"))
    )
    (net (code "46") (name "unconnected-(U$1A-GPIO_26-PadP8.14)") (class "Default")
      (node (ref "U$1") (pin "P8.14") (pinfunction "GPIO_26_P8.14") (pintype "bidirectional"))
    )
    (net (code "47") (name "unconnected-(U$1A-GPIO_27-PadP8.17)") (class "Default")
      (node (ref "U$1") (pin "P8.17") (pinfunction "GPIO_27_P8.17") (pintype "bidirectional"))
    )
    (net (code "48") (name "unconnected-(U$1A-GPIO_32-PadP8.25)") (class "Default")
      (node (ref "U$1") (pin "P8.25") (pinfunction "GPIO_32_P8.25") (pintype "bidirectional"))
    )
    (net (code "49") (name "unconnected-(U$1A-GPIO_33-PadP8.24)") (class "Default")
      (node (ref "U$1") (pin "P8.24") (pinfunction "GPIO_33_P8.24") (pintype "bidirectional"))
    )
    (net (code "50") (name "unconnected-(U$1A-GPIO_34-PadP8.5)") (class "Default")
      (node (ref "U$1") (pin "P8.5") (pinfunction "GPIO_34_P8.5") (pintype "bidirectional"))
    )
    (net (code "51") (name "unconnected-(U$1A-GPIO_35-PadP8.6)") (class "Default")
      (node (ref "U$1") (pin "P8.6") (pinfunction "GPIO_35_P8.6") (pintype "bidirectional"))
    )
    (net (code "52") (name "unconnected-(U$1A-GPIO_36-PadP8.23)") (class "Default")
      (node (ref "U$1") (pin "P8.23") (pinfunction "GPIO_36_P8.23") (pintype "bidirectional"))
    )
    (net (code "53") (name "unconnected-(U$1A-GPIO_37-PadP8.22)") (class "Default")
      (node (ref "U$1") (pin "P8.22") (pinfunction "GPIO_37_P8.22") (pintype "bidirectional"))
    )
    (net (code "54") (name "unconnected-(U$1A-GPIO_38-PadP8.3)") (class "Default")
      (node (ref "U$1") (pin "P8.3") (pinfunction "GPIO_38_P8.3") (pintype "bidirectional"))
    )
    (net (code "55") (name "unconnected-(U$1A-GPIO_39-PadP8.4)") (class "Default")
      (node (ref "U$1") (pin "P8.4") (pinfunction "GPIO_39_P8.4") (pintype "bidirectional"))
    )
    (net (code "56") (name "unconnected-(U$1A-GPIO_44-PadP8.12)") (class "Default")
      (node (ref "U$1") (pin "P8.12") (pinfunction "GPIO_44_P8.12") (pintype "bidirectional"))
    )
    (net (code "57") (name "unconnected-(U$1A-GPIO_45-PadP8.11)") (class "Default")
      (node (ref "U$1") (pin "P8.11") (pinfunction "GPIO_45_P8.11") (pintype "bidirectional"))
    )
    (net (code "58") (name "unconnected-(U$1A-GPIO_46-PadP8.16)") (class "Default")
      (node (ref "U$1") (pin "P8.16") (pinfunction "GPIO_46_P8.16") (pintype "bidirectional"))
    )
    (net (code "59") (name "unconnected-(U$1A-GPIO_47-PadP8.15)") (class "Default")
      (node (ref "U$1") (pin "P8.15") (pinfunction "GPIO_47_P8.15") (pintype "bidirectional"))
    )
    (net (code "60") (name "unconnected-(U$1A-GPIO_61-PadP8.26)") (class "Default")
      (node (ref "U$1") (pin "P8.26") (pinfunction "GPIO_61_P8.26") (pintype "bidirectional"))
    )
    (net (code "61") (name "unconnected-(U$1A-GPIO_62-PadP8.21)") (class "Default")
      (node (ref "U$1") (pin "P8.21") (pinfunction "GPIO_62_P8.21") (pintype "bidirectional"))
    )
    (net (code "62") (name "unconnected-(U$1A-GPIO_63-PadP8.20)") (class "Default")
      (node (ref "U$1") (pin "P8.20") (pinfunction "GPIO_63_P8.20") (pintype "bidirectional"))
    )
    (net (code "63") (name "unconnected-(U$1A-GPIO_65-PadP8.18)") (class "Default")
      (node (ref "U$1") (pin "P8.18") (pinfunction "GPIO_65_P8.18") (pintype "bidirectional"))
    )
    (net (code "64") (name "unconnected-(U$1A-GPIO_68-PadP8.10)") (class "Default")
      (node (ref "U$1") (pin "P8.10") (pinfunction "GPIO_68_P8.10") (pintype "bidirectional"))
    )
    (net (code "65") (name "unconnected-(U$1A-GPIO_69-PadP8.9)") (class "Default")
      (node (ref "U$1") (pin "P8.9") (pinfunction "GPIO_69_P8.9") (pintype "bidirectional"))
    )
    (net (code "66") (name "unconnected-(U$1A-GPIO_70-PadP8.45)") (class "Default")
      (node (ref "U$1") (pin "P8.45") (pinfunction "GPIO_70_P8.45") (pintype "bidirectional"))
    )
    (net (code "67") (name "unconnected-(U$1A-GPIO_71-PadP8.46)") (class "Default")
      (node (ref "U$1") (pin "P8.46") (pinfunction "GPIO_71_P8.46") (pintype "bidirectional"))
    )
    (net (code "68") (name "unconnected-(U$1A-GPIO_72-PadP8.43)") (class "Default")
      (node (ref "U$1") (pin "P8.43") (pinfunction "GPIO_72_P8.43") (pintype "bidirectional"))
    )
    (net (code "69") (name "unconnected-(U$1A-GPIO_73-PadP8.44)") (class "Default")
      (node (ref "U$1") (pin "P8.44") (pinfunction "GPIO_73_P8.44") (pintype "bidirectional"))
    )
    (net (code "70") (name "unconnected-(U$1A-GPIO_74-PadP8.41)") (class "Default")
      (node (ref "U$1") (pin "P8.41") (pinfunction "GPIO_74_P8.41") (pintype "bidirectional"))
    )
    (net (code "71") (name "unconnected-(U$1A-GPIO_75-PadP8.42)") (class "Default")
      (node (ref "U$1") (pin "P8.42") (pinfunction "GPIO_75_P8.42") (pintype "bidirectional"))
    )
    (net (code "72") (name "unconnected-(U$1A-GPIO_76-PadP8.39)") (class "Default")
      (node (ref "U$1") (pin "P8.39") (pinfunction "GPIO_76_P8.39") (pintype "bidirectional"))
    )
    (net (code "73") (name "unconnected-(U$1A-GPIO_77-PadP8.40)") (class "Default")
      (node (ref "U$1") (pin "P8.40") (pinfunction "GPIO_77_P8.40") (pintype "bidirectional"))
    )
    (net (code "74") (name "unconnected-(U$1A-GPIO_78-PadP8.37)") (class "Default")
      (node (ref "U$1") (pin "P8.37") (pinfunction "GPIO_78_P8.37") (pintype "bidirectional"))
    )
    (net (code "75") (name "unconnected-(U$1A-GPIO_79-PadP8.38)") (class "Default")
      (node (ref "U$1") (pin "P8.38") (pinfunction "GPIO_79_P8.38") (pintype "bidirectional"))
    )
    (net (code "76") (name "unconnected-(U$1A-GPIO_80-PadP8.36)") (class "Default")
      (node (ref "U$1") (pin "P8.36") (pinfunction "GPIO_80_P8.36") (pintype "bidirectional"))
    )
    (net (code "77") (name "unconnected-(U$1A-GPIO_81-PadP8.34)") (class "Default")
      (node (ref "U$1") (pin "P8.34") (pinfunction "GPIO_81_P8.34") (pintype "bidirectional"))
    )
    (net (code "78") (name "unconnected-(U$1A-GPIO_86-PadP8.27)") (class "Default")
      (node (ref "U$1") (pin "P8.27") (pinfunction "GPIO_86_P8.27") (pintype "bidirectional"))
    )
    (net (code "79") (name "unconnected-(U$1A-GPIO_87-PadP8.29)") (class "Default")
      (node (ref "U$1") (pin "P8.29") (pinfunction "GPIO_87_P8.29") (pintype "bidirectional"))
    )
    (net (code "80") (name "unconnected-(U$1A-GPIO_88-PadP8.28)") (class "Default")
      (node (ref "U$1") (pin "P8.28") (pinfunction "GPIO_88_P8.28") (pintype "bidirectional"))
    )
    (net (code "81") (name "unconnected-(U$1A-GPIO_89-PadP8.30)") (class "Default")
      (node (ref "U$1") (pin "P8.30") (pinfunction "GPIO_89_P8.30") (pintype "bidirectional"))
    )
    (net (code "82") (name "unconnected-(U$1B-AIN0-PadP9.39)") (class "Default")
      (node (ref "U$1") (pin "P9.39") (pinfunction "AIN0_P9.39") (pintype "bidirectional"))
    )
    (net (code "83") (name "unconnected-(U$1B-AIN1-PadP9.40)") (class "Default")
      (node (ref "U$1") (pin "P9.40") (pinfunction "AIN1_P9.40") (pintype "bidirectional"))
    )
    (net (code "84") (name "unconnected-(U$1B-AIN2-PadP9.37)") (class "Default")
      (node (ref "U$1") (pin "P9.37") (pinfunction "AIN2_P9.37") (pintype "bidirectional"))
    )
    (net (code "85") (name "unconnected-(U$1B-AIN3-PadP9.38)") (class "Default")
      (node (ref "U$1") (pin "P9.38") (pinfunction "AIN3_P9.38") (pintype "bidirectional"))
    )
    (net (code "86") (name "unconnected-(U$1B-AIN4-PadP9.33)") (class "Default")
      (node (ref "U$1") (pin "P9.33") (pinfunction "AIN4_P9.33") (pintype "bidirectional"))
    )
    (net (code "87") (name "unconnected-(U$1B-AIN5-PadP9.36)") (class "Default")
      (node (ref "U$1") (pin "P9.36") (pinfunction "AIN5_P9.36") (pintype "bidirectional"))
    )
    (net (code "88") (name "unconnected-(U$1B-AIN6-PadP9.35)") (class "Default")
      (node (ref "U$1") (pin "P9.35") (pinfunction "AIN6_P9.35") (pintype "bidirectional"))
    )
    (net (code "89") (name "unconnected-(U$1B-GNDA_ADC-PadP9.34)") (class "Default")
      (node (ref "U$1") (pin "P9.34") (pinfunction "GNDA_ADC_P9.34") (pintype "bidirectional"))
    )
    (net (code "90") (name "unconnected-(U$1B-GPIO_2-PadP9.22)") (class "Default")
      (node (ref "U$1") (pin "P9.22") (pinfunction "GPIO_2_P9.22") (pintype "bidirectional"))
    )
    (net (code "91") (name "unconnected-(U$1B-GPIO_3-PadP9.21)") (class "Default")
      (node (ref "U$1") (pin "P9.21") (pinfunction "GPIO_3_P9.21") (pintype "bidirectional"))
    )
    (net (code "92") (name "unconnected-(U$1B-GPIO_4-PadP9.17)") (class "Default")
      (node (ref "U$1") (pin "P9.17") (pinfunction "GPIO_4_P9.17") (pintype "bidirectional"))
    )
    (net (code "93") (name "unconnected-(U$1B-GPIO_5-PadP9.18)") (class "Default")
      (node (ref "U$1") (pin "P9.18") (pinfunction "GPIO_5_P9.18") (pintype "bidirectional"))
    )
    (net (code "94") (name "unconnected-(U$1B-GPIO_7-PadP9.42)") (class "Default")
      (node (ref "U$1") (pin "P9.42") (pinfunction "GPIO_7_P9.42") (pintype "bidirectional"))
    )
    (net (code "95") (name "unconnected-(U$1B-GPIO_14-PadP9.26)") (class "Default")
      (node (ref "U$1") (pin "P9.26") (pinfunction "GPIO_14_P9.26") (pintype "bidirectional"))
    )
    (net (code "96") (name "unconnected-(U$1B-GPIO_15-PadP9.24)") (class "Default")
      (node (ref "U$1") (pin "P9.24") (pinfunction "GPIO_15_P9.24") (pintype "bidirectional"))
    )
    (net (code "97") (name "unconnected-(U$1B-GPIO_20-PadP9.41)") (class "Default")
      (node (ref "U$1") (pin "P9.41") (pinfunction "GPIO_20_P9.41") (pintype "bidirectional"))
    )
    (net (code "98") (name "unconnected-(U$1B-GPIO_30-PadP9.11)") (class "Default")
      (node (ref "U$1") (pin "P9.11") (pinfunction "GPIO_30_P9.11") (pintype "bidirectional"))
    )
    (net (code "99") (name "unconnected-(U$1B-GPIO_31-PadP9.13)") (class "Default")
      (node (ref "U$1") (pin "P9.13") (pinfunction "GPIO_31_P9.13") (pintype "bidirectional"))
    )
    (net (code "100") (name "unconnected-(U$1B-GPIO_40-PadP9.14)") (class "Default")
      (node (ref "U$1") (pin "P9.14") (pinfunction "GPIO_40_P9.14") (pintype "bidirectional"))
    )
    (net (code "101") (name "unconnected-(U$1B-GPIO_48-PadP9.15)") (class "Default")
      (node (ref "U$1") (pin "P9.15") (pinfunction "GPIO_48_P9.15") (pintype "bidirectional"))
    )
    (net (code "102") (name "unconnected-(U$1B-GPIO_49-PadP9.23)") (class "Default")
      (node (ref "U$1") (pin "P9.23") (pinfunction "GPIO_49_P9.23") (pintype "bidirectional"))
    )
    (net (code "103") (name "unconnected-(U$1B-GPIO_51-PadP9.16)") (class "Default")
      (node (ref "U$1") (pin "P9.16") (pinfunction "GPIO_51_P9.16") (pintype "bidirectional"))
    )
    (net (code "104") (name "unconnected-(U$1B-GPIO_60-PadP9.12)") (class "Default")
      (node (ref "U$1") (pin "P9.12") (pinfunction "GPIO_60_P9.12") (pintype "bidirectional"))
    )
    (net (code "105") (name "unconnected-(U$1B-GPIO_117-PadP9.25)") (class "Default")
      (node (ref "U$1") (pin "P9.25") (pinfunction "GPIO_117_P9.25") (pintype "bidirectional"))
    )
    (net (code "106") (name "unconnected-(U$1B-GPIO_120-PadP9.31)") (class "Default")
      (node (ref "U$1") (pin "P9.31") (pinfunction "GPIO_120_P9.31") (pintype "bidirectional"))
    )
    (net (code "107") (name "unconnected-(U$1B-GPIO_121-PadP9.29)") (class "Default")
      (node (ref "U$1") (pin "P9.29") (pinfunction "GPIO_121_P9.29") (pintype "bidirectional"))
    )
    (net (code "108") (name "unconnected-(U$1B-GPIO_122-PadP9.30)") (class "Default")
      (node (ref "U$1") (pin "P9.30") (pinfunction "GPIO_122_P9.30") (pintype "bidirectional"))
    )
    (net (code "109") (name "unconnected-(U$1B-GPIO_123-PadP9.28)") (class "Default")
      (node (ref "U$1") (pin "P9.28") (pinfunction "GPIO_123_P9.28") (pintype "bidirectional"))
    )
    (net (code "110") (name "unconnected-(U$1B-GPIO_125-PadP9.27)") (class "Default")
      (node (ref "U$1") (pin "P9.27") (pinfunction "GPIO_125_P9.27") (pintype "bidirectional"))
    )
    (net (code "111") (name "unconnected-(U$1B-I2C2_SCL-PadP9.19)") (class "Default")
      (node (ref "U$1") (pin "P9.19") (pinfunction "I2C2_SCL_P9.19") (pintype "bidirectional"))
    )
    (net (code "112") (name "unconnected-(U$1B-I2C2_SDA-PadP9.20)") (class "Default")
      (node (ref "U$1") (pin "P9.20") (pinfunction "I2C2_SDA_P9.20") (pintype "bidirectional"))
    )
    (net (code "113") (name "unconnected-(U$1B-SYS_5V-PadP9.7)") (class "Default")
      (node (ref "U$1") (pin "P9.7") (pinfunction "SYS_5V_P9.7") (pintype "bidirectional"))
    )
    (net (code "114") (name "unconnected-(U$1B-SYS_5V-PadP9.8)") (class "Default")
      (node (ref "U$1") (pin "P9.8") (pinfunction "SYS_5V_P9.8") (pintype "bidirectional"))
    )
    (net (code "115") (name "unconnected-(U$1B-SYS_RESET~{N}-PadP9.10)") (class "Default")
      (node (ref "U$1") (pin "P9.10") (pinfunction "SYS_RESET~{N}_P9.10") (pintype "bidirectional"))
    )
    (net (code "116") (name "unconnected-(U$1B-VDD_3V3-PadP9.3)") (class "Default")
      (node (ref "U$1") (pin "P9.3") (pinfunction "VDD_3V3_P9.3") (pintype "bidirectional"))
    )
    (net (code "117") (name "unconnected-(U$1B-VDD_3V3-PadP9.4)") (class "Default")
      (node (ref "U$1") (pin "P9.4") (pinfunction "VDD_3V3_P9.4") (pintype "bidirectional"))
    )
    (net (code "118") (name "unconnected-(U$1B-VDD_ADC-PadP9.32)") (class "Default")
      (node (ref "U$1") (pin "P9.32") (pinfunction "VDD_ADC_P9.32") (pintype "bidirectional"))
    )
    (net (code "119") (name "unconnected-(U$6-RC2{slash}AN6-Pad8)") (class "Default")
      (node (ref "U$6") (pin "8") (pinfunction "RC2/AN6_8") (pintype "bidirectional"))
    )
  )
)
